# SystemStatusBoard.net
KiCad netlist of a schematic drawn in Altium Designer
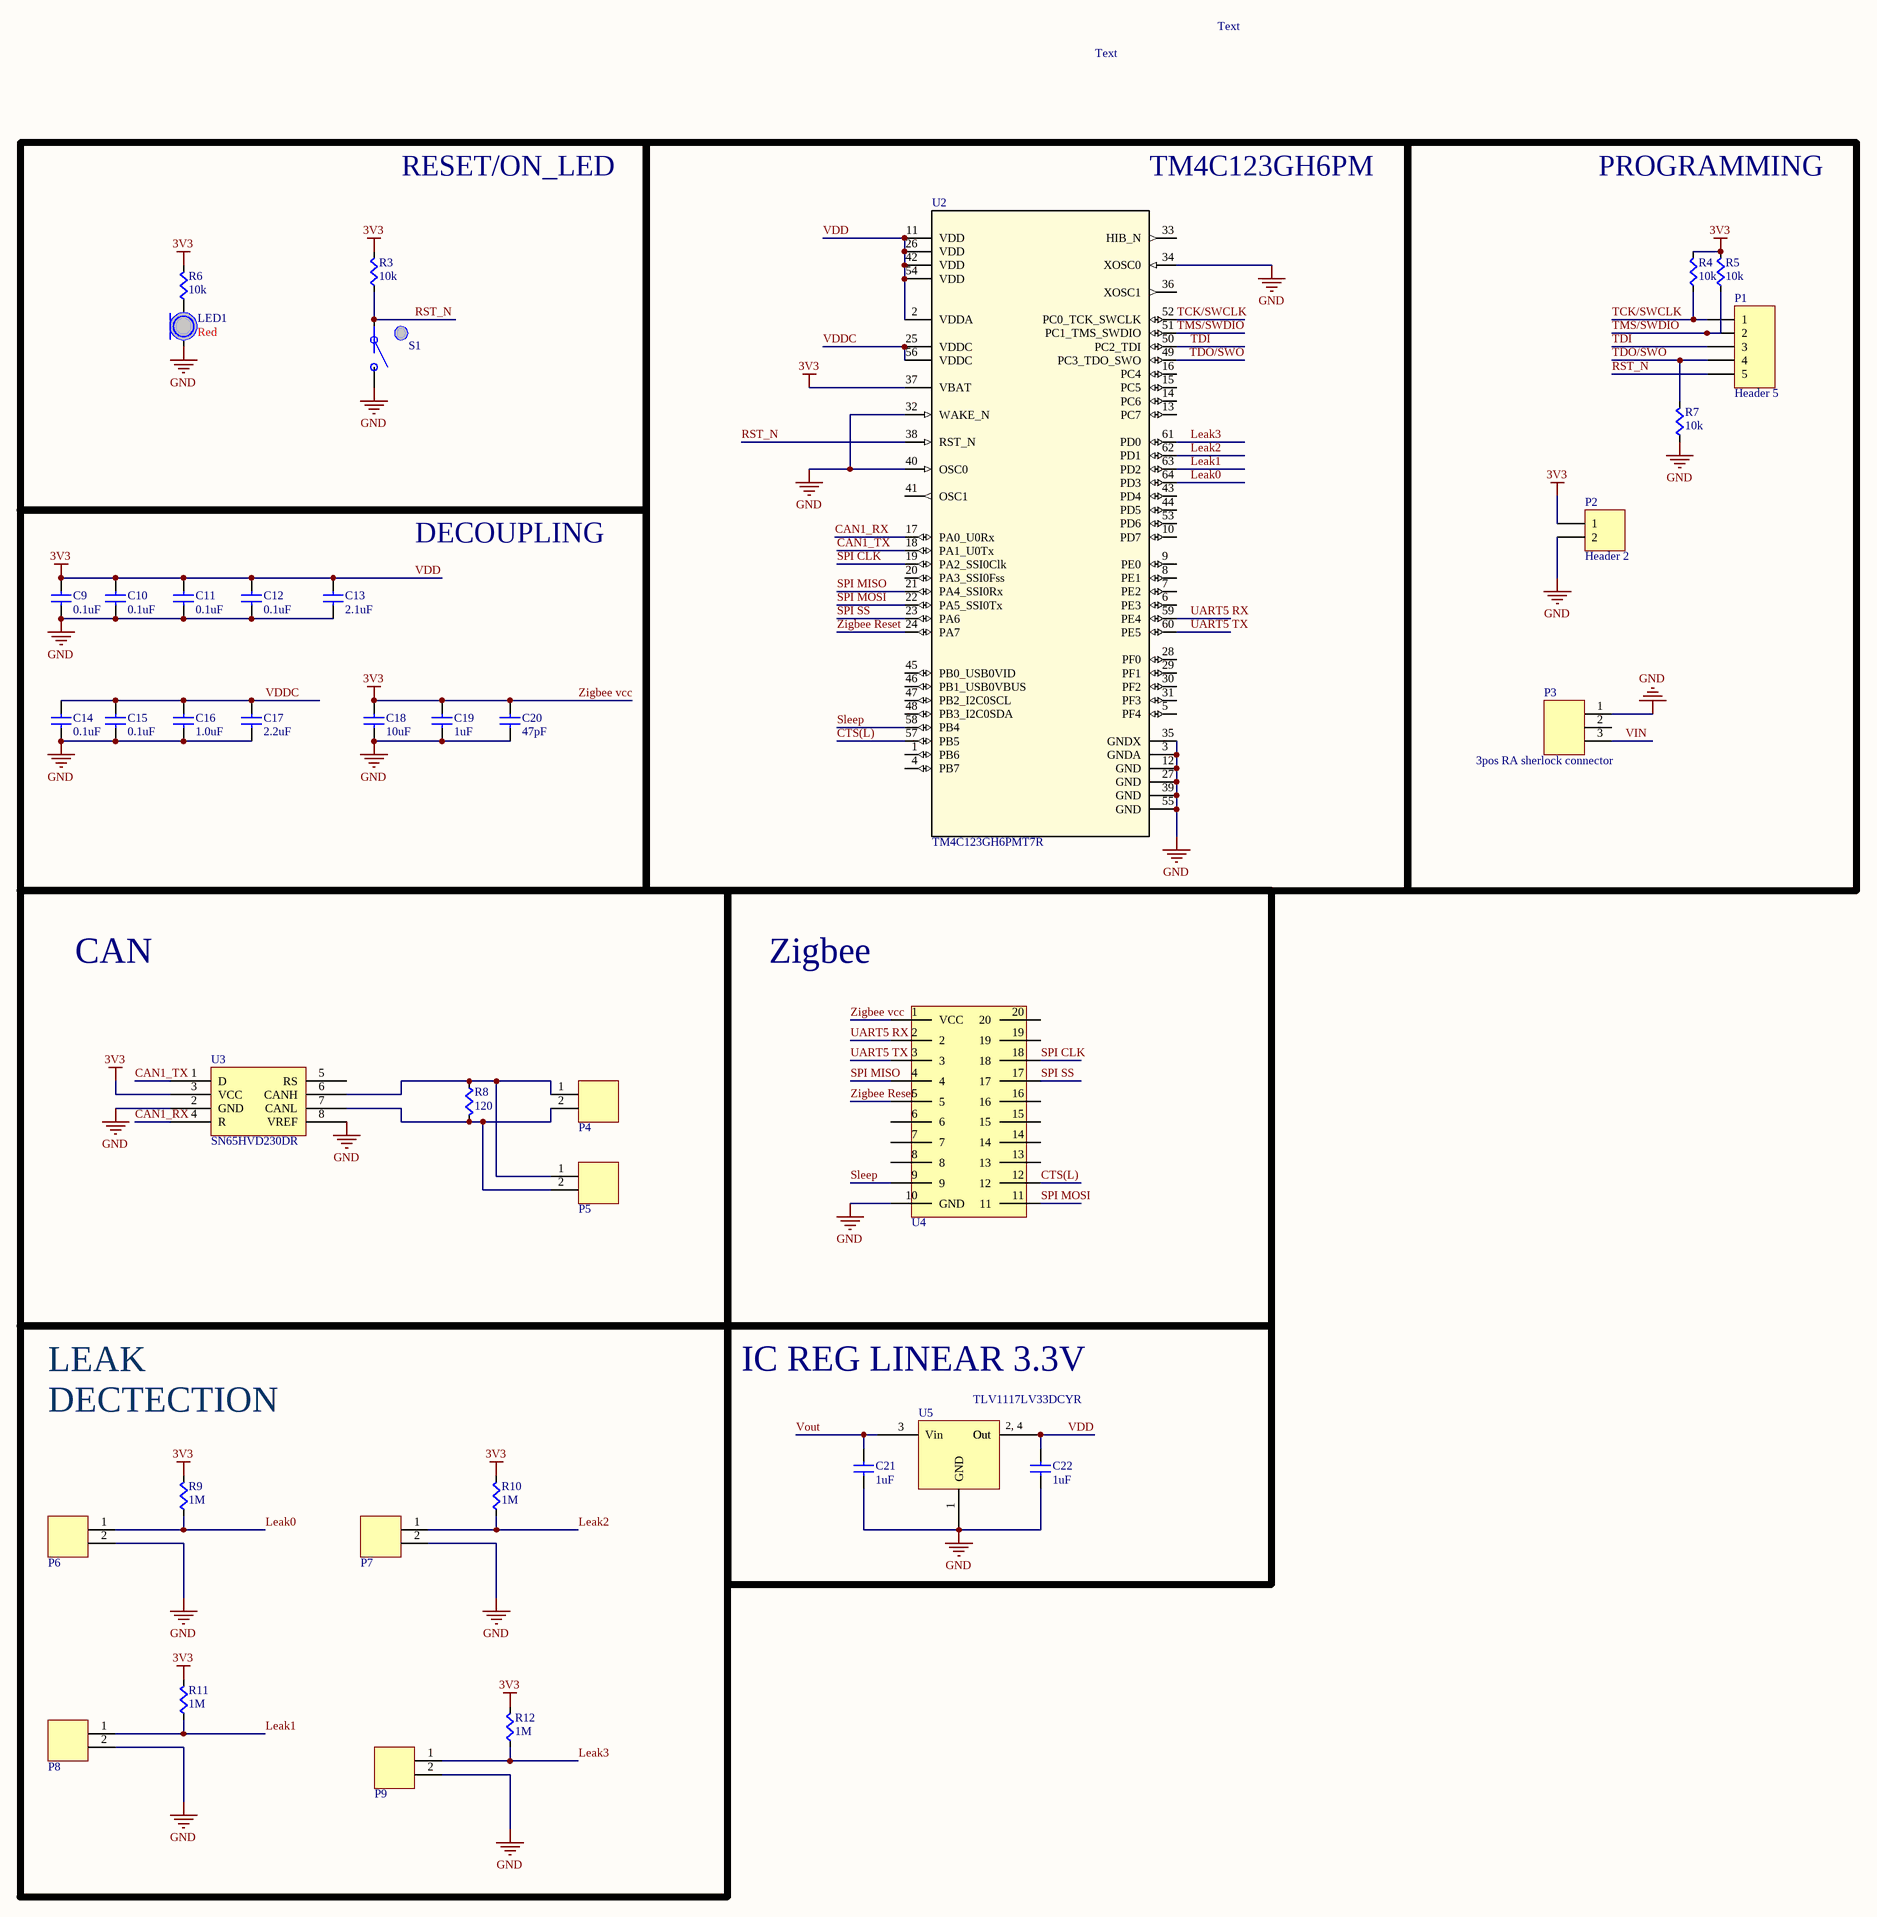
[diagram p0: SystemStatusBoard.SchDoc]

(export (version "E")
  (design (tool "Eeschema 10.0.6"))
  (components
    (comp (ref "C9")
      (value "0.1uF")
      (footprint "CAPC0603")
      (fields (field (name "Comment") "Cap"))
      (libsource (lib "SubjuGator8") (part "Cap"))
    )
    (comp (ref "C10")
      (value "0.1uF")
      (footprint "CAPC0603")
      (fields (field (name "Comment") "Cap"))
      (libsource (lib "SubjuGator8") (part "Cap"))
    )
    (comp (ref "C11")
      (value "0.1uF")
      (footprint "CAPC0603")
      (fields (field (name "Comment") "Cap"))
      (libsource (lib "SubjuGator8") (part "Cap"))
    )
    (comp (ref "C12")
      (value "0.1uF")
      (footprint "CAPC0603")
      (fields (field (name "Comment") "Cap"))
      (libsource (lib "SubjuGator8") (part "Cap"))
    )
    (comp (ref "C13")
      (value "2.1uF")
      (footprint "CAPC0603")
      (fields (field (name "Comment") "Cap"))
      (libsource (lib "SubjuGator8") (part "Cap"))
    )
    (comp (ref "C14")
      (value "0.1uF")
      (footprint "CAPC0603")
      (fields (field (name "Comment") "Cap"))
      (libsource (lib "SubjuGator8") (part "Cap"))
    )
    (comp (ref "C15")
      (value "0.1uF")
      (footprint "CAPC0603")
      (fields (field (name "Comment") "Cap"))
      (libsource (lib "SubjuGator8") (part "Cap"))
    )
    (comp (ref "C16")
      (value "1.0uF")
      (footprint "CAPC0603")
      (fields (field (name "Comment") "Cap"))
      (libsource (lib "SubjuGator8") (part "Cap"))
    )
    (comp (ref "C17")
      (value "2.2uF")
      (footprint "CAPC0603")
      (fields (field (name "Comment") "Cap"))
      (libsource (lib "SubjuGator8") (part "Cap"))
    )
    (comp (ref "C18")
      (value "10uF")
      (footprint "CAPC0603")
      (fields (field (name "Comment") "Cap"))
      (libsource (lib "Passives") (part "Cap"))
    )
    (comp (ref "C19")
      (value "1uF")
      (footprint "CAPC0603")
      (fields (field (name "Comment") "Cap"))
      (libsource (lib "Passives") (part "Cap"))
    )
    (comp (ref "C20")
      (value "47pF")
      (footprint "CAPC0603")
      (fields (field (name "Comment") "Cap"))
      (libsource (lib "Passives") (part "Cap"))
    )
    (comp (ref "C21")
      (value "1uF")
      (footprint "CAPC0603")
      (fields (field (name "MANUFACTURER PART NUMBER") "C0603C105K8PACTU") (field (name "Comment") "Cap"))
      (libsource (lib "SubjuGator8") (part "Cap"))
    )
    (comp (ref "C22")
      (value "1uF")
      (footprint "CAPC0603")
      (fields (field (name "MANUFACTURER PART NUMBER") "C0603C105K8PACTU") (field (name "Comment") "Cap"))
      (libsource (lib "SubjuGator8") (part "Cap"))
    )
    (comp (ref "LED1")
      (value "LED")
      (footprint "LED0603")
      (fields (field (name "COLOR") "Red"))
      (libsource (lib "SubjuGator8") (part "LED"))
    )
    (comp (ref "P1")
      (value "Header 5")
      (footprint "HDR1X5")
      (description "Header, 5-Pin")
      (fields (field (name "PUBLISHER") "Altium Limited"))
      (libsource (lib "Miscellaneous Connectors") (part "Header 5"))
    )
    (comp (ref "P2")
      (value "Header 2")
      (footprint "HDR1X2")
      (description "Header, 2-Pin")
      (fields (field (name "PUBLISHER") "Altium Limited"))
      (libsource (lib "Miscellaneous Connectors") (part "Header 2"))
    )
    (comp (ref "P3")
      (value "3pos RA sherlock connector")
      (footprint "MOLEX-HDR-1X3-SHERLOCK-RA")
      (description "Header, Molex, 2mm Pitch Sherlock Header, Single Row, Right Angle 3 Circuits, Length 3.3mm")
      (fields
        (field (name "MANUFACTURER PART NUMBER") "35363-0360")
        (field (name "MANUFACTURER") "Molex Connector Corporation")
      )
      (libsource (lib "Connectors") (part "MOLEX-HDR-1x3-SHERLOCK_RA"))
    )
    (comp (ref "P4")
      (value "2-pin Horz Sherlock")
      (footprint "MOLEX-HDR-1X2-SHERLOCK-HORZ")
      (fields
        (field (name "MANUFACTURER PART NUMBER") "0353630260")
        (field (name "MANUFACTURER") "Molex Inc")
      )
      (libsource (lib "SubjuGator8") (part "MOLEX-HDR-1x2-SHERLOCK_RA"))
    )
    (comp (ref "P5")
      (value "2-pin Horz Sherlock")
      (footprint "MOLEX-HDR-1X2-SHERLOCK-HORZ")
      (fields
        (field (name "MANUFACTURER PART NUMBER") "0353630260")
        (field (name "MANUFACTURER") "Molex Inc")
      )
      (libsource (lib "SubjuGator8") (part "MOLEX-HDR-1x2-SHERLOCK_RA"))
    )
    (comp (ref "P6")
      (value "2-pin Vert Sherlock")
      (footprint "MOLEX-HDR-1X2-SHERLOCK-VERT")
      (libsource (lib "SubjuGator8") (part "MOLEX-HDR-1x2-SHERLOCK_VERT"))
    )
    (comp (ref "P7")
      (value "2-pin Vert Sherlock")
      (footprint "MOLEX-HDR-1X2-SHERLOCK-VERT")
      (libsource (lib "SubjuGator8") (part "MOLEX-HDR-1x2-SHERLOCK_VERT"))
    )
    (comp (ref "P8")
      (value "2-pin Vert Sherlock")
      (footprint "MOLEX-HDR-1X2-SHERLOCK-VERT")
      (libsource (lib "SubjuGator8") (part "MOLEX-HDR-1x2-SHERLOCK_VERT"))
    )
    (comp (ref "P9")
      (value "2-pin Vert Sherlock")
      (footprint "MOLEX-HDR-1X2-SHERLOCK-VERT")
      (libsource (lib "SubjuGator8") (part "MOLEX-HDR-1x2-SHERLOCK_VERT"))
    )
    (comp (ref "R3")
      (value "10k")
      (footprint "RES0603")
      (fields (field (name "Comment") "Res"))
      (libsource (lib "SubjuGator8") (part "Res"))
    )
    (comp (ref "R4")
      (value "10k")
      (footprint "RES0603")
      (fields (field (name "Comment") "Res"))
      (libsource (lib "SubjuGator8") (part "Res"))
    )
    (comp (ref "R5")
      (value "10k")
      (footprint "RES0603")
      (fields (field (name "Comment") "Res"))
      (libsource (lib "SubjuGator8") (part "Res"))
    )
    (comp (ref "R6")
      (value "10k")
      (footprint "RES0603")
      (fields (field (name "Comment") "Res"))
      (libsource (lib "SubjuGator8") (part "Res"))
    )
    (comp (ref "R7")
      (value "10k")
      (footprint "RES0603")
      (fields (field (name "Comment") "Res"))
      (libsource (lib "SubjuGator8") (part "Res"))
    )
    (comp (ref "R8")
      (value "120")
      (footprint "RES0603")
      (fields (field (name "Comment") "Res"))
      (libsource (lib "SubjuGator8") (part "Res"))
    )
    (comp (ref "R9")
      (value "1M")
      (footprint "RES0603")
      (fields (field (name "Comment") "Res"))
      (libsource (lib "SubjuGator8") (part "Res"))
    )
    (comp (ref "R10")
      (value "1M")
      (footprint "RES0603")
      (fields (field (name "Comment") "Res"))
      (libsource (lib "SubjuGator8") (part "Res"))
    )
    (comp (ref "R11")
      (value "1M")
      (footprint "RES0603")
      (fields (field (name "Comment") "Res"))
      (libsource (lib "SubjuGator8") (part "Res"))
    )
    (comp (ref "R12")
      (value "1M")
      (footprint "RES0603")
      (fields (field (name "Comment") "Res"))
      (libsource (lib "SubjuGator8") (part "Res"))
    )
    (comp (ref "S1")
      (value "Button")
      (footprint "PTS645xxxxSMTR92")
      (description "SPST Button")
      (libsource (lib "SubjuGator8") (part "Button"))
    )
    (comp (ref "U2")
      (value "TM4C123GH6PMT7R")
      (footprint "PM0064A_N")
      (description "Imported")
      (fields
        (field (name "PARTNUMBER") "TM4C123GH6PMTR")
        (field (name "ALTERNATE_PARTNUMBER") "TM4C123GH6PMT")
      )
      (libsource (lib "TivaC") (part "TM4C123GH6PMT7R"))
    )
    (comp (ref "U3")
      (value "SN65HVD230DR")
      (footprint "SOIC-8pin")
      (description "IC TXRX CAN 1MBPS 3.3V 8SOIC")
      (libsource (lib "SubjuGator8") (part "SN65HVD230DR"))
    )
    (comp (ref "U4")
      (value "XBee")
      (footprint "XBee")
      (description "XBee radio")
      (libsource (lib "ICs") (part "XBee"))
    )
    (comp (ref "U5")
      (value "TLV1117LV33DCYR")
      (footprint "SOT23-4N")
      (description "IC REG LINEAR 3.3V 1A SOT223-4")
      (fields (field (name "DIGI-KEY PART NUMBER") "296-28778-1-ND"))
      (libsource (lib "ICs") (part "TLV1117LV33DCYR"))
    )
  )
  (nets
    (net (code "1") (name "/CAN1_RX") (class "Default")
      (node (ref "U2") (pin "17") (pinfunction "PA0_U0Rx_17") (pintype "bidirectional"))
      (node (ref "U3") (pin "4") (pinfunction "R_4") (pintype "passive"))
    )
    (net (code "2") (name "/CAN1_TX") (class "Default")
      (node (ref "U2") (pin "18") (pinfunction "PA1_U0Tx_18") (pintype "bidirectional"))
      (node (ref "U3") (pin "1") (pinfunction "D_1") (pintype "passive"))
    )
    (net (code "3") (name "/CTS(L)") (class "Default")
      (node (ref "U2") (pin "57") (pinfunction "PB5_57") (pintype "bidirectional"))
      (node (ref "U4") (pin "12") (pinfunction "12_12") (pintype "passive"))
    )
    (net (code "4") (name "/Leak0") (class "Default")
      (node (ref "P6") (pin "1") (pinfunction "1_1") (pintype "passive"))
      (node (ref "R9") (pin "2") (pinfunction "B_2") (pintype "passive"))
      (node (ref "U2") (pin "64") (pinfunction "PD3_64") (pintype "bidirectional"))
    )
    (net (code "5") (name "/Leak1") (class "Default")
      (node (ref "P8") (pin "1") (pinfunction "1_1") (pintype "passive"))
      (node (ref "R11") (pin "2") (pinfunction "B_2") (pintype "passive"))
      (node (ref "U2") (pin "63") (pinfunction "PD2_63") (pintype "bidirectional"))
    )
    (net (code "6") (name "/Leak2") (class "Default")
      (node (ref "P7") (pin "1") (pinfunction "1_1") (pintype "passive"))
      (node (ref "R10") (pin "2") (pinfunction "B_2") (pintype "passive"))
      (node (ref "U2") (pin "62") (pinfunction "PD1_62") (pintype "bidirectional"))
    )
    (net (code "7") (name "/Leak3") (class "Default")
      (node (ref "P9") (pin "1") (pinfunction "1_1") (pintype "passive"))
      (node (ref "R12") (pin "2") (pinfunction "B_2") (pintype "passive"))
      (node (ref "U2") (pin "61") (pinfunction "PD0_61") (pintype "bidirectional"))
    )
    (net (code "8") (name "/RST_N") (class "Default")
      (node (ref "P1") (pin "5") (pinfunction "5_5") (pintype "passive"))
      (node (ref "R3") (pin "2") (pinfunction "B_2") (pintype "passive"))
      (node (ref "S1") (pin "A") (pinfunction "A_A") (pintype "passive"))
      (node (ref "U2") (pin "38") (pinfunction "RST_N_38") (pintype "input"))
    )
    (net (code "9") (name "/SPI CLK") (class "Default")
      (node (ref "U2") (pin "19") (pinfunction "PA2_SSI0Clk_19") (pintype "bidirectional"))
      (node (ref "U4") (pin "18") (pinfunction "18_18") (pintype "passive"))
    )
    (net (code "10") (name "/SPI MISO") (class "Default")
      (node (ref "U2") (pin "21") (pinfunction "PA4_SSI0Rx_21") (pintype "bidirectional"))
      (node (ref "U4") (pin "4") (pinfunction "4_4") (pintype "passive"))
    )
    (net (code "11") (name "/SPI MOSI") (class "Default")
      (node (ref "U2") (pin "22") (pinfunction "PA5_SSI0Tx_22") (pintype "bidirectional"))
      (node (ref "U4") (pin "11") (pinfunction "11_11") (pintype "passive"))
    )
    (net (code "12") (name "/SPI SS") (class "Default")
      (node (ref "U2") (pin "23") (pinfunction "PA6_23") (pintype "bidirectional"))
      (node (ref "U4") (pin "17") (pinfunction "17_17") (pintype "passive"))
    )
    (net (code "13") (name "/Sleep") (class "Default")
      (node (ref "U2") (pin "58") (pinfunction "PB4_58") (pintype "bidirectional"))
      (node (ref "U4") (pin "9") (pinfunction "9_9") (pintype "passive"))
    )
    (net (code "14") (name "/TCK{slash}SWCLK") (class "Default")
      (node (ref "P1") (pin "1") (pinfunction "1_1") (pintype "passive"))
      (node (ref "R4") (pin "2") (pinfunction "B_2") (pintype "passive"))
      (node (ref "U2") (pin "52") (pinfunction "PC0_TCK_SWCLK_52") (pintype "bidirectional"))
    )
    (net (code "15") (name "/TDI") (class "Default")
      (node (ref "P1") (pin "3") (pinfunction "3_3") (pintype "passive"))
      (node (ref "U2") (pin "50") (pinfunction "PC2_TDI_50") (pintype "bidirectional"))
    )
    (net (code "16") (name "/TDO{slash}SWO") (class "Default")
      (node (ref "P1") (pin "4") (pinfunction "4_4") (pintype "passive"))
      (node (ref "R7") (pin "1") (pinfunction "A_1") (pintype "passive"))
      (node (ref "U2") (pin "49") (pinfunction "PC3_TDO_SWO_49") (pintype "bidirectional"))
    )
    (net (code "17") (name "/TMS{slash}SWDIO") (class "Default")
      (node (ref "P1") (pin "2") (pinfunction "2_2") (pintype "passive"))
      (node (ref "R5") (pin "2") (pinfunction "B_2") (pintype "passive"))
      (node (ref "U2") (pin "51") (pinfunction "PC1_TMS_SWDIO_51") (pintype "bidirectional"))
    )
    (net (code "18") (name "/UART5 RX") (class "Default")
      (node (ref "U2") (pin "59") (pinfunction "PE4_59") (pintype "bidirectional"))
      (node (ref "U4") (pin "2") (pinfunction "2_2") (pintype "passive"))
    )
    (net (code "19") (name "/UART5 TX") (class "Default")
      (node (ref "U2") (pin "60") (pinfunction "PE5_60") (pintype "bidirectional"))
      (node (ref "U4") (pin "3") (pinfunction "3_3") (pintype "passive"))
    )
    (net (code "20") (name "/VDDC") (class "Default")
      (node (ref "C14") (pin "1") (pinfunction "A_1") (pintype "passive"))
      (node (ref "C15") (pin "1") (pinfunction "A_1") (pintype "passive"))
      (node (ref "C16") (pin "1") (pinfunction "A_1") (pintype "passive"))
      (node (ref "C17") (pin "1") (pinfunction "A_1") (pintype "passive"))
      (node (ref "U2") (pin "25") (pinfunction "VDDC_25") (pintype "power_in"))
      (node (ref "U2") (pin "56") (pinfunction "VDDC_56") (pintype "power_in"))
    )
    (net (code "21") (name "/VIN") (class "Default")
      (node (ref "P3") (pin "3") (pinfunction "3_3") (pintype "passive"))
    )
    (net (code "22") (name "/Vout") (class "Default")
      (node (ref "C21") (pin "1") (pinfunction "A_1") (pintype "passive"))
      (node (ref "U5") (pin "3") (pinfunction "Vin_3") (pintype "passive"))
    )
    (net (code "23") (name "/Zigbee Reset") (class "Default")
      (node (ref "U2") (pin "24") (pinfunction "PA7_24") (pintype "bidirectional"))
      (node (ref "U4") (pin "5") (pinfunction "5_5") (pintype "passive"))
    )
    (net (code "24") (name "3V3") (class "Default")
      (node (ref "C10") (pin "1") (pinfunction "A_1") (pintype "passive"))
      (node (ref "C11") (pin "1") (pinfunction "A_1") (pintype "passive"))
      (node (ref "C12") (pin "1") (pinfunction "A_1") (pintype "passive"))
      (node (ref "C13") (pin "1") (pinfunction "A_1") (pintype "passive"))
      (node (ref "C18") (pin "1") (pinfunction "A_1") (pintype "passive"))
      (node (ref "C19") (pin "1") (pinfunction "A_1") (pintype "passive"))
      (node (ref "C20") (pin "1") (pinfunction "A_1") (pintype "passive"))
      (node (ref "C22") (pin "1") (pinfunction "A_1") (pintype "passive"))
      (node (ref "C9") (pin "1") (pinfunction "A_1") (pintype "passive"))
      (node (ref "P2") (pin "1") (pinfunction "1_1") (pintype "passive"))
      (node (ref "R10") (pin "1") (pinfunction "A_1") (pintype "passive"))
      (node (ref "R11") (pin "1") (pinfunction "A_1") (pintype "passive"))
      (node (ref "R12") (pin "1") (pinfunction "A_1") (pintype "passive"))
      (node (ref "R3") (pin "1") (pinfunction "A_1") (pintype "passive"))
      (node (ref "R4") (pin "1") (pinfunction "A_1") (pintype "passive"))
      (node (ref "R5") (pin "1") (pinfunction "A_1") (pintype "passive"))
      (node (ref "R6") (pin "1") (pinfunction "A_1") (pintype "passive"))
      (node (ref "R9") (pin "1") (pinfunction "A_1") (pintype "passive"))
      (node (ref "U2") (pin "11") (pinfunction "VDD_11") (pintype "power_in"))
      (node (ref "U2") (pin "2") (pinfunction "VDDA_2") (pintype "power_in"))
      (node (ref "U2") (pin "26") (pinfunction "VDD_26") (pintype "power_in"))
      (node (ref "U2") (pin "37") (pinfunction "VBAT_37") (pintype "power_in"))
      (node (ref "U2") (pin "42") (pinfunction "VDD_42") (pintype "power_in"))
      (node (ref "U2") (pin "54") (pinfunction "VDD_54") (pintype "power_in"))
      (node (ref "U3") (pin "3") (pinfunction "VCC_3") (pintype "passive"))
      (node (ref "U4") (pin "1") (pinfunction "VCC_1") (pintype "passive"))
      (node (ref "U5") (pin "2") (pinfunction "Out_2") (pintype "passive"))
      (node (ref "U5") (pin "4") (pinfunction "Out_4") (pintype "passive"))
    )
    (net (code "25") (name "GND") (class "Default")
      (node (ref "C10") (pin "2") (pinfunction "B_2") (pintype "passive"))
      (node (ref "C11") (pin "2") (pinfunction "B_2") (pintype "passive"))
      (node (ref "C12") (pin "2") (pinfunction "B_2") (pintype "passive"))
      (node (ref "C13") (pin "2") (pinfunction "B_2") (pintype "passive"))
      (node (ref "C14") (pin "2") (pinfunction "B_2") (pintype "passive"))
      (node (ref "C15") (pin "2") (pinfunction "B_2") (pintype "passive"))
      (node (ref "C16") (pin "2") (pinfunction "B_2") (pintype "passive"))
      (node (ref "C17") (pin "2") (pinfunction "B_2") (pintype "passive"))
      (node (ref "C18") (pin "2") (pinfunction "B_2") (pintype "passive"))
      (node (ref "C19") (pin "2") (pinfunction "B_2") (pintype "passive"))
      (node (ref "C20") (pin "2") (pinfunction "B_2") (pintype "passive"))
      (node (ref "C21") (pin "2") (pinfunction "B_2") (pintype "passive"))
      (node (ref "C22") (pin "2") (pinfunction "B_2") (pintype "passive"))
      (node (ref "C9") (pin "2") (pinfunction "B_2") (pintype "passive"))
      (node (ref "LED1") (pin "C") (pinfunction "C_C") (pintype "passive"))
      (node (ref "P2") (pin "2") (pinfunction "2_2") (pintype "passive"))
      (node (ref "P3") (pin "1") (pinfunction "1_1") (pintype "passive"))
      (node (ref "P6") (pin "2") (pinfunction "2_2") (pintype "passive"))
      (node (ref "P7") (pin "2") (pinfunction "2_2") (pintype "passive"))
      (node (ref "P8") (pin "2") (pinfunction "2_2") (pintype "passive"))
      (node (ref "P9") (pin "2") (pinfunction "2_2") (pintype "passive"))
      (node (ref "R7") (pin "2") (pinfunction "B_2") (pintype "passive"))
      (node (ref "S1") (pin "B") (pinfunction "B_B") (pintype "passive"))
      (node (ref "U2") (pin "12") (pinfunction "GND_12") (pintype "power_in"))
      (node (ref "U2") (pin "27") (pinfunction "GND_27") (pintype "power_in"))
      (node (ref "U2") (pin "3") (pinfunction "GNDA_3") (pintype "power_in"))
      (node (ref "U2") (pin "32") (pinfunction "WAKE_N_32") (pintype "input"))
      (node (ref "U2") (pin "34") (pinfunction "XOSC0_34") (pintype "input"))
      (node (ref "U2") (pin "35") (pinfunction "GNDX_35") (pintype "power_in"))
      (node (ref "U2") (pin "39") (pinfunction "GND_39") (pintype "power_in"))
      (node (ref "U2") (pin "40") (pinfunction "OSC0_40") (pintype "input"))
      (node (ref "U2") (pin "55") (pinfunction "GND_55") (pintype "power_in"))
      (node (ref "U3") (pin "2") (pinfunction "GND_2") (pintype "passive"))
      (node (ref "U3") (pin "8") (pinfunction "VREF_8") (pintype "passive"))
      (node (ref "U4") (pin "10") (pinfunction "GND_10") (pintype "passive"))
      (node (ref "U5") (pin "1") (pinfunction "GND_1") (pintype "passive"))
    )
    (net (code "26") (name "Net-(R6-B)") (class "Default")
      (node (ref "LED1") (pin "A") (pinfunction "A_A") (pintype "passive"))
      (node (ref "R6") (pin "2") (pinfunction "B_2") (pintype "passive"))
    )
    (net (code "27") (name "Net-(R8-A)") (class "Default")
      (node (ref "P4") (pin "2") (pinfunction "2_2") (pintype "passive"))
      (node (ref "P5") (pin "2") (pinfunction "2_2") (pintype "passive"))
      (node (ref "R8") (pin "1") (pinfunction "A_1") (pintype "passive"))
      (node (ref "U3") (pin "7") (pinfunction "CANL_7") (pintype "passive"))
    )
    (net (code "28") (name "Net-(R8-B)") (class "Default")
      (node (ref "P4") (pin "1") (pinfunction "1_1") (pintype "passive"))
      (node (ref "P5") (pin "1") (pinfunction "1_1") (pintype "passive"))
      (node (ref "R8") (pin "2") (pinfunction "B_2") (pintype "passive"))
      (node (ref "U3") (pin "6") (pinfunction "CANH_6") (pintype "passive"))
    )
    (net (code "29") (name "unconnected-(P3-Pad2)") (class "Default")
      (node (ref "P3") (pin "2") (pinfunction "2_2") (pintype "passive"))
    )
    (net (code "30") (name "unconnected-(U2-HIB_N-Pad33)") (class "Default")
      (node (ref "U2") (pin "33") (pinfunction "HIB_N_33") (pintype "output"))
    )
    (net (code "31") (name "unconnected-(U2-OSC1-Pad41)") (class "Default")
      (node (ref "U2") (pin "41") (pinfunction "OSC1_41") (pintype "output"))
    )
    (net (code "32") (name "unconnected-(U2-PA3_SSI0Fss-Pad20)") (class "Default")
      (node (ref "U2") (pin "20") (pinfunction "PA3_SSI0Fss_20") (pintype "bidirectional"))
    )
    (net (code "33") (name "unconnected-(U2-PB0_USB0VID-Pad45)") (class "Default")
      (node (ref "U2") (pin "45") (pinfunction "PB0_USB0VID_45") (pintype "bidirectional"))
    )
    (net (code "34") (name "unconnected-(U2-PB1_USB0VBUS-Pad46)") (class "Default")
      (node (ref "U2") (pin "46") (pinfunction "PB1_USB0VBUS_46") (pintype "bidirectional"))
    )
    (net (code "35") (name "unconnected-(U2-PB2_I2C0SCL-Pad47)") (class "Default")
      (node (ref "U2") (pin "47") (pinfunction "PB2_I2C0SCL_47") (pintype "bidirectional"))
    )
    (net (code "36") (name "unconnected-(U2-PB3_I2C0SDA-Pad48)") (class "Default")
      (node (ref "U2") (pin "48") (pinfunction "PB3_I2C0SDA_48") (pintype "bidirectional"))
    )
    (net (code "37") (name "unconnected-(U2-PB6-Pad1)") (class "Default")
      (node (ref "U2") (pin "1") (pinfunction "PB6_1") (pintype "bidirectional"))
    )
    (net (code "38") (name "unconnected-(U2-PB7-Pad4)") (class "Default")
      (node (ref "U2") (pin "4") (pinfunction "PB7_4") (pintype "bidirectional"))
    )
    (net (code "39") (name "unconnected-(U2-PC4-Pad16)") (class "Default")
      (node (ref "U2") (pin "16") (pinfunction "PC4_16") (pintype "bidirectional"))
    )
    (net (code "40") (name "unconnected-(U2-PC5-Pad15)") (class "Default")
      (node (ref "U2") (pin "15") (pinfunction "PC5_15") (pintype "bidirectional"))
    )
    (net (code "41") (name "unconnected-(U2-PC6-Pad14)") (class "Default")
      (node (ref "U2") (pin "14") (pinfunction "PC6_14") (pintype "bidirectional"))
    )
    (net (code "42") (name "unconnected-(U2-PC7-Pad13)") (class "Default")
      (node (ref "U2") (pin "13") (pinfunction "PC7_13") (pintype "bidirectional"))
    )
    (net (code "43") (name "unconnected-(U2-PD4-Pad43)") (class "Default")
      (node (ref "U2") (pin "43") (pinfunction "PD4_43") (pintype "bidirectional"))
    )
    (net (code "44") (name "unconnected-(U2-PD5-Pad44)") (class "Default")
      (node (ref "U2") (pin "44") (pinfunction "PD5_44") (pintype "bidirectional"))
    )
    (net (code "45") (name "unconnected-(U2-PD6-Pad53)") (class "Default")
      (node (ref "U2") (pin "53") (pinfunction "PD6_53") (pintype "bidirectional"))
    )
    (net (code "46") (name "unconnected-(U2-PD7-Pad10)") (class "Default")
      (node (ref "U2") (pin "10") (pinfunction "PD7_10") (pintype "bidirectional"))
    )
    (net (code "47") (name "unconnected-(U2-PE0-Pad9)") (class "Default")
      (node (ref "U2") (pin "9") (pinfunction "PE0_9") (pintype "bidirectional"))
    )
    (net (code "48") (name "unconnected-(U2-PE1-Pad8)") (class "Default")
      (node (ref "U2") (pin "8") (pinfunction "PE1_8") (pintype "bidirectional"))
    )
    (net (code "49") (name "unconnected-(U2-PE2-Pad7)") (class "Default")
      (node (ref "U2") (pin "7") (pinfunction "PE2_7") (pintype "bidirectional"))
    )
    (net (code "50") (name "unconnected-(U2-PE3-Pad6)") (class "Default")
      (node (ref "U2") (pin "6") (pinfunction "PE3_6") (pintype "bidirectional"))
    )
    (net (code "51") (name "unconnected-(U2-PF0-Pad28)") (class "Default")
      (node (ref "U2") (pin "28") (pinfunction "PF0_28") (pintype "bidirectional"))
    )
    (net (code "52") (name "unconnected-(U2-PF1-Pad29)") (class "Default")
      (node (ref "U2") (pin "29") (pinfunction "PF1_29") (pintype "bidirectional"))
    )
    (net (code "53") (name "unconnected-(U2-PF2-Pad30)") (class "Default")
      (node (ref "U2") (pin "30") (pinfunction "PF2_30") (pintype "bidirectional"))
    )
    (net (code "54") (name "unconnected-(U2-PF3-Pad31)") (class "Default")
      (node (ref "U2") (pin "31") (pinfunction "PF3_31") (pintype "bidirectional"))
    )
    (net (code "55") (name "unconnected-(U2-PF4-Pad5)") (class "Default")
      (node (ref "U2") (pin "5") (pinfunction "PF4_5") (pintype "bidirectional"))
    )
    (net (code "56") (name "unconnected-(U2-XOSC1-Pad36)") (class "Default")
      (node (ref "U2") (pin "36") (pinfunction "XOSC1_36") (pintype "output"))
    )
    (net (code "57") (name "unconnected-(U3-RS-Pad5)") (class "Default")
      (node (ref "U3") (pin "5") (pinfunction "RS_5") (pintype "passive"))
    )
    (net (code "58") (name "unconnected-(U4-Pad6)") (class "Default")
      (node (ref "U4") (pin "6") (pinfunction "6_6") (pintype "passive"))
    )
    (net (code "59") (name "unconnected-(U4-Pad7)") (class "Default")
      (node (ref "U4") (pin "7") (pinfunction "7_7") (pintype "passive"))
    )
    (net (code "60") (name "unconnected-(U4-Pad8)") (class "Default")
      (node (ref "U4") (pin "8") (pinfunction "8_8") (pintype "passive"))
    )
    (net (code "61") (name "unconnected-(U4-Pad13)") (class "Default")
      (node (ref "U4") (pin "13") (pinfunction "13_13") (pintype "passive"))
    )
    (net (code "62") (name "unconnected-(U4-Pad14)") (class "Default")
      (node (ref "U4") (pin "14") (pinfunction "14_14") (pintype "passive"))
    )
    (net (code "63") (name "unconnected-(U4-Pad15)") (class "Default")
      (node (ref "U4") (pin "15") (pinfunction "15_15") (pintype "passive"))
    )
    (net (code "64") (name "unconnected-(U4-Pad16)") (class "Default")
      (node (ref "U4") (pin "16") (pinfunction "16_16") (pintype "passive"))
    )
    (net (code "65") (name "unconnected-(U4-Pad19)") (class "Default")
      (node (ref "U4") (pin "19") (pinfunction "19_19") (pintype "passive"))
    )
    (net (code "66") (name "unconnected-(U4-Pad20)") (class "Default")
      (node (ref "U4") (pin "20") (pinfunction "20_20") (pintype "passive"))
    )
  )
)
